# SRLatch.net
KiCad netlist of a schematic drawn in Altium Designer
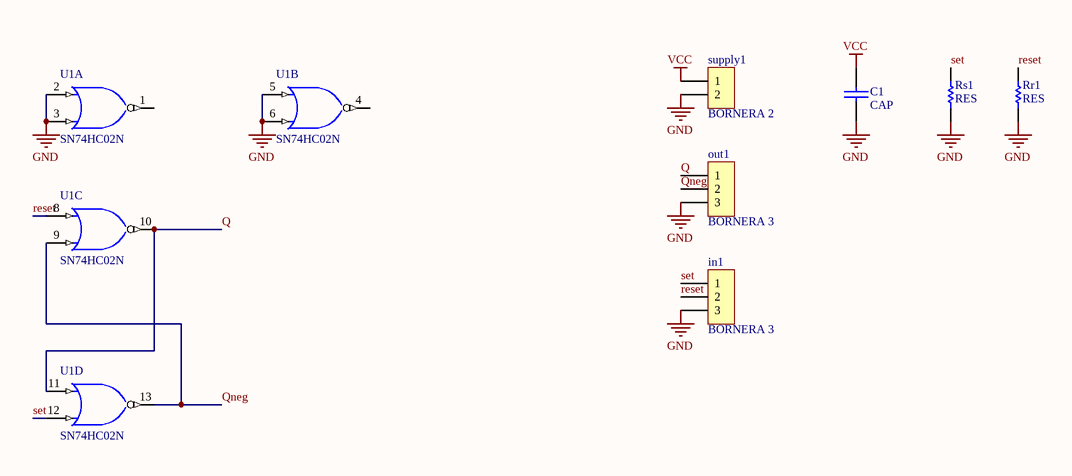
[diagram p0: SRLatch.SchDoc]

(export (version "E")
  (design (tool "Eeschema 10.0.6"))
  (components
    (comp (ref "C1") (value "CAP") (footprint "CAP100") (libsource (lib "LIBEBAL") (part "CAP")))
    (comp (ref "in1")
      (value "BORNERA 3")
      (footprint "BORNERA3")
      (libsource (lib "LIBEBAL") (part "BORNERA 3"))
    )
    (comp (ref "out1")
      (value "BORNERA 3")
      (footprint "BORNERA3")
      (libsource (lib "LIBEBAL") (part "BORNERA 3"))
    )
    (comp (ref "Rr1") (value "RES") (footprint "0805") (libsource (lib "LIBEBAL") (part "RES")))
    (comp (ref "Rs1") (value "RES") (footprint "0805") (libsource (lib "LIBEBAL") (part "RES")))
    (comp (ref "supply1")
      (value "BORNERA 2")
      (footprint "BORNERA2")
      (libsource (lib "LIBEBAL") (part "BORNERA 2"))
    )
    (comp (ref "U1")
      (value "SN74HC02N")
      (footprint "N014")
      (description "Quadruple 2-Input Positive-NOR Gate")
      (fields (field (name "PUBLISHER") "Altium Limited"))
      (libsource (lib "TI Logic Gate 2") (part "SN74HC02N"))
    )
  )
  (nets
    (net (code "1") (name "/Q") (class "Default")
      (node (ref "U1") (pin "10") (pinfunction "Y_10") (pintype "output"))
      (node (ref "U1") (pin "11") (pinfunction "A_11") (pintype "input"))
      (node (ref "out1") (pin "1") (pinfunction "1_1") (pintype "passive"))
    )
    (net (code "2") (name "/Qneg") (class "Default")
      (node (ref "U1") (pin "13") (pinfunction "Y_13") (pintype "output"))
      (node (ref "U1") (pin "9") (pinfunction "B_9") (pintype "input"))
      (node (ref "out1") (pin "2") (pinfunction "2_2") (pintype "passive"))
    )
    (net (code "3") (name "/reset") (class "Default")
      (node (ref "Rr1") (pin "2") (pinfunction "2_2") (pintype "passive"))
      (node (ref "U1") (pin "8") (pinfunction "A_8") (pintype "input"))
      (node (ref "in1") (pin "2") (pinfunction "2_2") (pintype "passive"))
    )
    (net (code "4") (name "/set") (class "Default")
      (node (ref "Rs1") (pin "2") (pinfunction "2_2") (pintype "passive"))
      (node (ref "U1") (pin "12") (pinfunction "B_12") (pintype "input"))
      (node (ref "in1") (pin "1") (pinfunction "1_1") (pintype "passive"))
    )
    (net (code "5") (name "GND") (class "Default")
      (node (ref "C1") (pin "2") (pinfunction "2_2") (pintype "passive"))
      (node (ref "Rr1") (pin "1") (pinfunction "1_1") (pintype "passive"))
      (node (ref "Rs1") (pin "1") (pinfunction "1_1") (pintype "passive"))
      (node (ref "U1") (pin "2") (pinfunction "A_2") (pintype "input"))
      (node (ref "U1") (pin "3") (pinfunction "B_3") (pintype "input"))
      (node (ref "U1") (pin "5") (pinfunction "A_5") (pintype "input"))
      (node (ref "U1") (pin "6") (pinfunction "B_6") (pintype "input"))
      (node (ref "U1") (pin "7") (pinfunction "GND_7") (pintype "power_in"))
      (node (ref "in1") (pin "3") (pinfunction "3_3") (pintype "passive"))
      (node (ref "out1") (pin "3") (pinfunction "3_3") (pintype "passive"))
      (node (ref "supply1") (pin "2") (pinfunction "2_2") (pintype "passive"))
    )
    (net (code "6") (name "VCC") (class "Default")
      (node (ref "C1") (pin "1") (pinfunction "1_1") (pintype "passive"))
      (node (ref "U1") (pin "14") (pinfunction "VCC_14") (pintype "power_in"))
      (node (ref "supply1") (pin "1") (pinfunction "1_1") (pintype "passive"))
    )
    (net (code "7") (name "unconnected-(U1A-Y-Pad1)") (class "Default")
      (node (ref "U1") (pin "1") (pinfunction "Y_1") (pintype "output"))
    )
    (net (code "8") (name "unconnected-(U1B-Y-Pad4)") (class "Default")
      (node (ref "U1") (pin "4") (pinfunction "Y_4") (pintype "output"))
    )
  )
)
